# Sheet2.net
KiCad netlist of a schematic drawn in Altium Designer
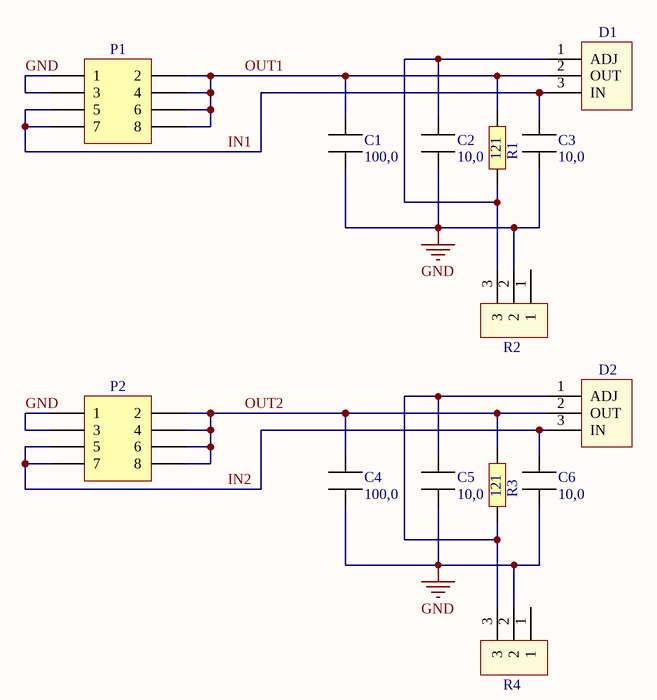
[diagram p0: Sheet2.SchDoc]

(export (version "E")
  (design (tool "Eeschema 10.0.6"))
  (components
    (comp (ref "C1") (value "100,0") (footprint "Cap_BIG") (libsource (lib "Schlib") (part "CAP_BIG")))
    (comp (ref "C2") (value "10,0") (footprint "Cap_BIG") (libsource (lib "Schlib") (part "CAP_BIG")))
    (comp (ref "C3") (value "10,0") (footprint "Cap_BIG") (libsource (lib "Schlib") (part "CAP_BIG")))
    (comp (ref "C4") (value "100,0") (footprint "Cap_BIG") (libsource (lib "Schlib") (part "CAP_BIG")))
    (comp (ref "C5") (value "10,0") (footprint "Cap_BIG") (libsource (lib "Schlib") (part "CAP_BIG")))
    (comp (ref "C6") (value "10,0") (footprint "Cap_BIG") (libsource (lib "Schlib") (part "CAP_BIG")))
    (comp (ref "D1") (value "LM1117-ADJ") (footprint "LM1117") (libsource (lib "Schlib") (part "LM1117-ADJ")))
    (comp (ref "D2") (value "LM1117-ADJ") (footprint "LM1117") (libsource (lib "Schlib") (part "LM1117-ADJ")))
    (comp (ref "P1")
      (value "Header 4X2")
      (footprint "HDR2X4")
      (description "Header, 4-Pin, Dual row")
      (fields (field (name "PUBLISHER") "Altium Limited"))
      (libsource (lib "Miscellaneous Connectors") (part "Header 4X2"))
    )
    (comp (ref "P2")
      (value "Header 4X2")
      (footprint "HDR2X4")
      (description "Header, 4-Pin, Dual row")
      (fields (field (name "PUBLISHER") "Altium Limited"))
      (libsource (lib "Miscellaneous Connectors") (part "Header 4X2"))
    )
    (comp (ref "R1") (value "121") (footprint "RES") (libsource (lib "Schlib") (part "RES")))
    (comp (ref "R2")
      (value "3296")
      (footprint "PODSTR_RES_3296")
      (libsource (lib "Schlib") (part "PODSTR_RES_NEW"))
    )
    (comp (ref "R3") (value "121") (footprint "RES") (libsource (lib "Schlib") (part "RES")))
    (comp (ref "R4")
      (value "3296")
      (footprint "PODSTR_RES_3296")
      (libsource (lib "Schlib") (part "PODSTR_RES_NEW"))
    )
  )
  (nets
    (net (code "1") (name "/IN1") (class "Default")
      (node (ref "C3") (pin "2") (pinfunction "2_2") (pintype "passive"))
      (node (ref "D1") (pin "3") (pinfunction "IN_3") (pintype "passive"))
      (node (ref "P1") (pin "5") (pinfunction "5_5") (pintype "passive"))
      (node (ref "P1") (pin "7") (pinfunction "7_7") (pintype "passive"))
    )
    (net (code "2") (name "/IN2") (class "Default")
      (node (ref "C6") (pin "2") (pinfunction "2_2") (pintype "passive"))
      (node (ref "D2") (pin "3") (pinfunction "IN_3") (pintype "passive"))
      (node (ref "P2") (pin "5") (pinfunction "5_5") (pintype "passive"))
      (node (ref "P2") (pin "7") (pinfunction "7_7") (pintype "passive"))
    )
    (net (code "3") (name "/OUT1") (class "Default")
      (node (ref "C1") (pin "2") (pinfunction "2_2") (pintype "passive"))
      (node (ref "D1") (pin "2") (pinfunction "OUT_2") (pintype "passive"))
      (node (ref "P1") (pin "2") (pinfunction "2_2") (pintype "passive"))
      (node (ref "P1") (pin "4") (pinfunction "4_4") (pintype "passive"))
      (node (ref "P1") (pin "6") (pinfunction "6_6") (pintype "passive"))
      (node (ref "P1") (pin "8") (pinfunction "8_8") (pintype "passive"))
      (node (ref "R1") (pin "2") (pinfunction "2_2") (pintype "passive"))
    )
    (net (code "4") (name "/OUT2") (class "Default")
      (node (ref "C4") (pin "2") (pinfunction "2_2") (pintype "passive"))
      (node (ref "D2") (pin "2") (pinfunction "OUT_2") (pintype "passive"))
      (node (ref "P2") (pin "2") (pinfunction "2_2") (pintype "passive"))
      (node (ref "P2") (pin "4") (pinfunction "4_4") (pintype "passive"))
      (node (ref "P2") (pin "6") (pinfunction "6_6") (pintype "passive"))
      (node (ref "P2") (pin "8") (pinfunction "8_8") (pintype "passive"))
      (node (ref "R3") (pin "2") (pinfunction "2_2") (pintype "passive"))
    )
    (net (code "5") (name "GND") (class "Default")
      (node (ref "C1") (pin "1") (pinfunction "1_1") (pintype "passive"))
      (node (ref "C2") (pin "1") (pinfunction "1_1") (pintype "passive"))
      (node (ref "C3") (pin "1") (pinfunction "1_1") (pintype "passive"))
      (node (ref "C4") (pin "1") (pinfunction "1_1") (pintype "passive"))
      (node (ref "C5") (pin "1") (pinfunction "1_1") (pintype "passive"))
      (node (ref "C6") (pin "1") (pinfunction "1_1") (pintype "passive"))
      (node (ref "P1") (pin "1") (pinfunction "1_1") (pintype "passive"))
      (node (ref "P1") (pin "3") (pinfunction "3_3") (pintype "passive"))
      (node (ref "P2") (pin "1") (pinfunction "1_1") (pintype "passive"))
      (node (ref "P2") (pin "3") (pinfunction "3_3") (pintype "passive"))
      (node (ref "R2") (pin "2") (pinfunction "2_2") (pintype "passive"))
      (node (ref "R4") (pin "2") (pinfunction "2_2") (pintype "passive"))
    )
    (net (code "6") (name "Net-(D1-ADJ)") (class "Default")
      (node (ref "C2") (pin "2") (pinfunction "2_2") (pintype "passive"))
      (node (ref "D1") (pin "1") (pinfunction "ADJ_1") (pintype "passive"))
      (node (ref "R1") (pin "1") (pinfunction "1_1") (pintype "passive"))
      (node (ref "R2") (pin "3") (pinfunction "3_3") (pintype "passive"))
    )
    (net (code "7") (name "Net-(D2-ADJ)") (class "Default")
      (node (ref "C5") (pin "2") (pinfunction "2_2") (pintype "passive"))
      (node (ref "D2") (pin "1") (pinfunction "ADJ_1") (pintype "passive"))
      (node (ref "R3") (pin "1") (pinfunction "1_1") (pintype "passive"))
      (node (ref "R4") (pin "3") (pinfunction "3_3") (pintype "passive"))
    )
    (net (code "8") (name "unconnected-(R2-Pad1)") (class "Default")
      (node (ref "R2") (pin "1") (pinfunction "1_1") (pintype "passive"))
    )
    (net (code "9") (name "unconnected-(R4-Pad1)") (class "Default")
      (node (ref "R4") (pin "1") (pinfunction "1_1") (pintype "passive"))
    )
  )
)
